# controller.net
KiCad netlist of a schematic drawn in EAGLE
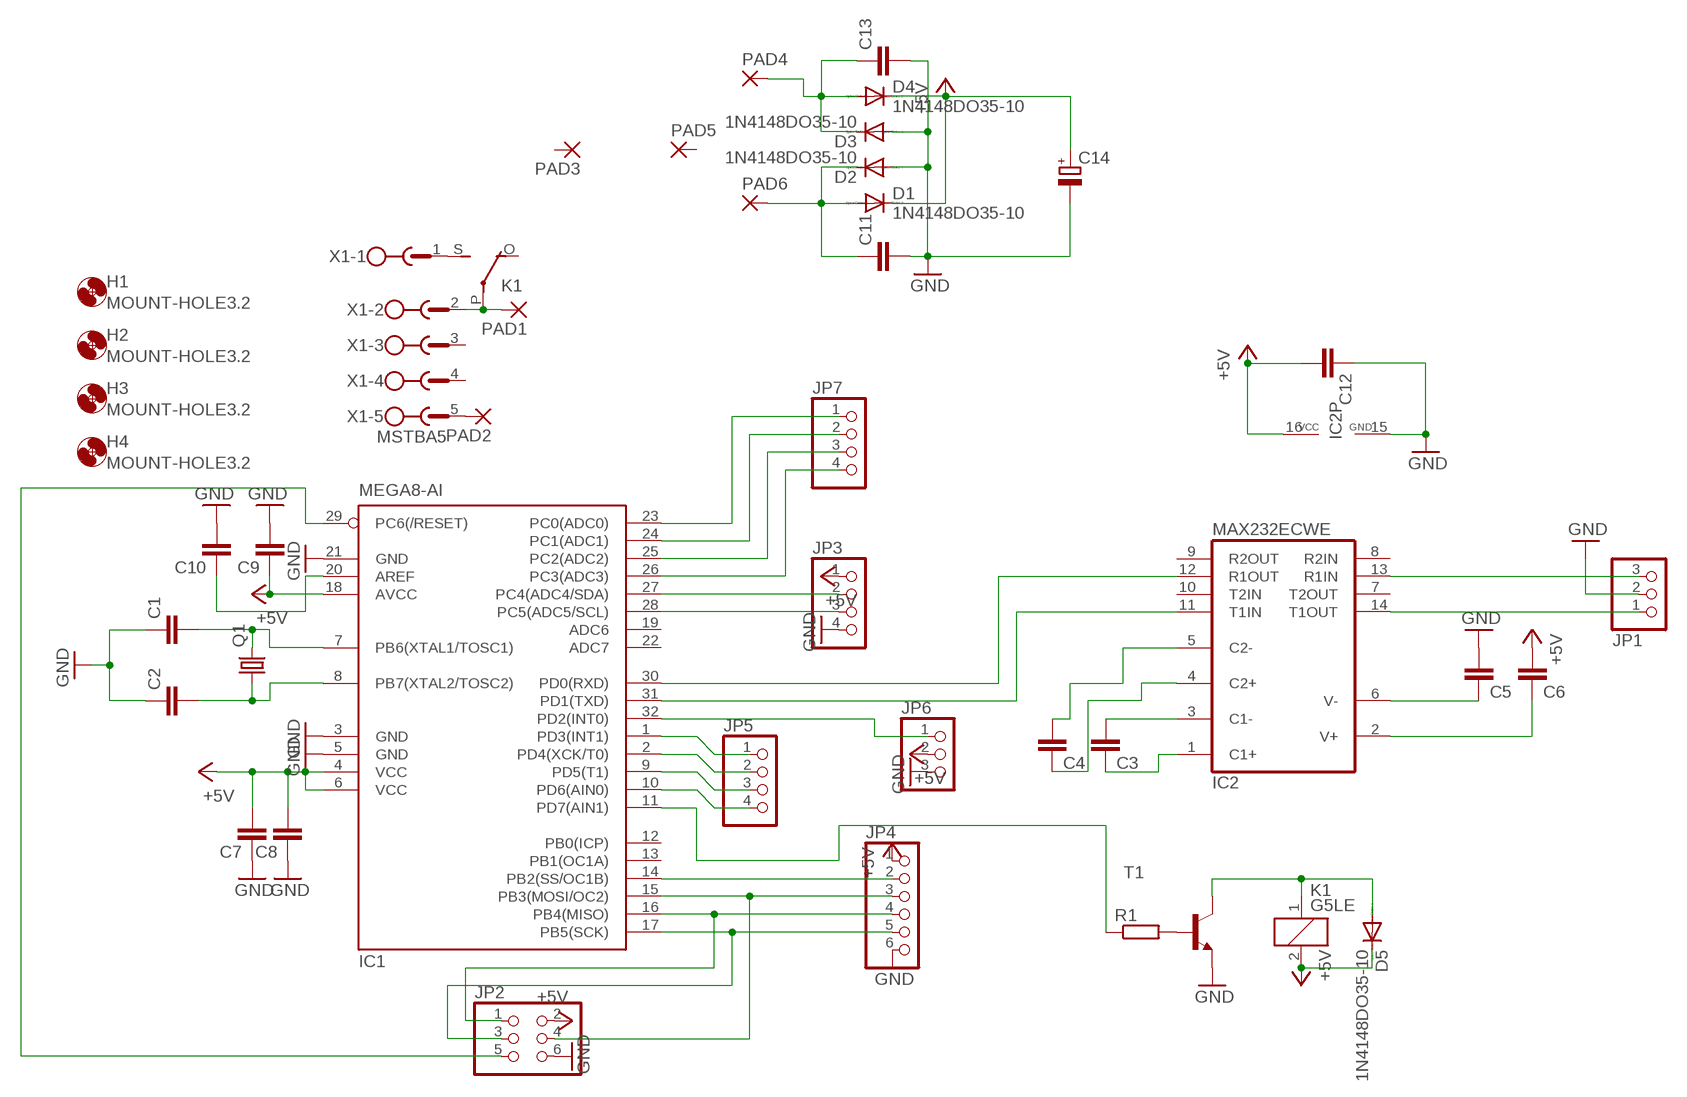
[diagram p0: schematic, sheet 1]

(export (version "E")
  (design (tool "Eeschema 10.0.6"))
  (components
    (comp (ref "C1")
      (value "C-EUC0805")
      (footprint "eagle-import:C0805")
      (libsource (lib "eagle-import") (part "C-EUC0805"))
    )
    (comp (ref "C2")
      (value "C-EUC0805")
      (footprint "eagle-import:C0805")
      (libsource (lib "eagle-import") (part "C-EUC0805"))
    )
    (comp (ref "C3")
      (value "C-EUC0805")
      (footprint "eagle-import:C0805")
      (libsource (lib "eagle-import") (part "C-EUC0805"))
    )
    (comp (ref "C4")
      (value "C-EUC0805")
      (footprint "eagle-import:C0805")
      (libsource (lib "eagle-import") (part "C-EUC0805"))
    )
    (comp (ref "C5")
      (value "C-EUC0805")
      (footprint "eagle-import:C0805")
      (libsource (lib "eagle-import") (part "C-EUC0805"))
    )
    (comp (ref "C6")
      (value "C-EUC0805")
      (footprint "eagle-import:C0805")
      (libsource (lib "eagle-import") (part "C-EUC0805"))
    )
    (comp (ref "C7")
      (value "C-EUC0805")
      (footprint "eagle-import:C0805")
      (libsource (lib "eagle-import") (part "C-EUC0805"))
    )
    (comp (ref "C8")
      (value "C-EUC0805")
      (footprint "eagle-import:C0805")
      (libsource (lib "eagle-import") (part "C-EUC0805"))
    )
    (comp (ref "C9")
      (value "C-EUC0805")
      (footprint "eagle-import:C0805")
      (libsource (lib "eagle-import") (part "C-EUC0805"))
    )
    (comp (ref "C10")
      (value "C-EUC0805")
      (footprint "eagle-import:C0805")
      (libsource (lib "eagle-import") (part "C-EUC0805"))
    )
    (comp (ref "C11")
      (value "C-EU050-025X075")
      (footprint "eagle-import:C050-025X075")
      (libsource (lib "eagle-import") (part "C-EU050-025X075"))
    )
    (comp (ref "C12")
      (value "C-EUC0805")
      (footprint "eagle-import:C0805")
      (libsource (lib "eagle-import") (part "C-EUC0805"))
    )
    (comp (ref "C13")
      (value "C-EU050-025X075")
      (footprint "eagle-import:C050-025X075")
      (libsource (lib "eagle-import") (part "C-EU050-025X075"))
    )
    (comp (ref "C14")
      (value "CPOL-EUE7.5-18")
      (footprint "eagle-import:E7,5-18")
      (libsource (lib "eagle-import") (part "CPOL-EUE7.5-18"))
    )
    (comp (ref "D1")
      (value "1N4148DO35-10")
      (footprint "eagle-import:DO35-10")
      (libsource (lib "eagle-import") (part "1N4148DO35-10"))
    )
    (comp (ref "D2")
      (value "1N4148DO35-10")
      (footprint "eagle-import:DO35-10")
      (libsource (lib "eagle-import") (part "1N4148DO35-10"))
    )
    (comp (ref "D3")
      (value "1N4148DO35-10")
      (footprint "eagle-import:DO35-10")
      (libsource (lib "eagle-import") (part "1N4148DO35-10"))
    )
    (comp (ref "D4")
      (value "1N4148DO35-10")
      (footprint "eagle-import:DO35-10")
      (libsource (lib "eagle-import") (part "1N4148DO35-10"))
    )
    (comp (ref "D5")
      (value "1N4148DO35-10")
      (footprint "eagle-import:DO35-10")
      (libsource (lib "eagle-import") (part "1N4148DO35-10"))
    )
    (comp (ref "H1")
      (value "MOUNT-HOLE3.2")
      (footprint "eagle-import:3,2")
      (libsource (lib "eagle-import") (part "MOUNT-HOLE3.2"))
    )
    (comp (ref "H2")
      (value "MOUNT-HOLE3.2")
      (footprint "eagle-import:3,2")
      (libsource (lib "eagle-import") (part "MOUNT-HOLE3.2"))
    )
    (comp (ref "H3")
      (value "MOUNT-HOLE3.2")
      (footprint "eagle-import:3,2")
      (libsource (lib "eagle-import") (part "MOUNT-HOLE3.2"))
    )
    (comp (ref "H4")
      (value "MOUNT-HOLE3.2")
      (footprint "eagle-import:3,2")
      (libsource (lib "eagle-import") (part "MOUNT-HOLE3.2"))
    )
    (comp (ref "IC1")
      (value "MEGA8-AI")
      (footprint "eagle-import:TQFP32-08")
      (fields (field (name "MPN") "ATMEGA8-16AU"))
      (libsource (lib "eagle-import") (part "MEGA8-AI"))
    )
    (comp (ref "IC2")
      (value "MAX232ECWE")
      (footprint "eagle-import:SO16")
      (libsource (lib "eagle-import") (part "MAX232ECWE"))
    )
    (comp (ref "JP1")
      (value "PINHD-1X3")
      (footprint "eagle-import:1X03")
      (libsource (lib "eagle-import") (part "PINHD-1X3"))
    )
    (comp (ref "JP2")
      (value "PINHD-2X3")
      (footprint "eagle-import:2X03")
      (libsource (lib "eagle-import") (part "PINHD-2X3"))
    )
    (comp (ref "JP3")
      (value "PINHD-1X4")
      (footprint "eagle-import:1X04")
      (libsource (lib "eagle-import") (part "PINHD-1X4"))
    )
    (comp (ref "JP4")
      (value "PINHD-1X6")
      (footprint "eagle-import:1X06")
      (libsource (lib "eagle-import") (part "PINHD-1X6"))
    )
    (comp (ref "JP5")
      (value "PINHD-1X4")
      (footprint "eagle-import:1X04")
      (libsource (lib "eagle-import") (part "PINHD-1X4"))
    )
    (comp (ref "JP6")
      (value "PINHD-1X3")
      (footprint "eagle-import:1X03")
      (libsource (lib "eagle-import") (part "PINHD-1X3"))
    )
    (comp (ref "JP7")
      (value "PINHD-1X4")
      (footprint "eagle-import:1X04")
      (libsource (lib "eagle-import") (part "PINHD-1X4"))
    )
    (comp (ref "K1")
      (value "G5LE")
      (footprint "eagle-import:G5LE")
      (libsource (lib "eagle-import") (part "G5LE"))
    )
    (comp (ref "PAD1")
      (value "3,81/1,4")
      (footprint "eagle-import:3,81_1,4")
      (libsource (lib "eagle-import") (part "3,81/1,4"))
    )
    (comp (ref "PAD2")
      (value "3,81/1,4")
      (footprint "eagle-import:3,81_1,4")
      (libsource (lib "eagle-import") (part "3,81/1,4"))
    )
    (comp (ref "PAD3")
      (value "3,81/1,4")
      (footprint "eagle-import:3,81_1,4")
      (libsource (lib "eagle-import") (part "3,81/1,4"))
    )
    (comp (ref "PAD4")
      (value "3,81/1,4")
      (footprint "eagle-import:3,81_1,4")
      (libsource (lib "eagle-import") (part "3,81/1,4"))
    )
    (comp (ref "PAD5")
      (value "3,81/1,4")
      (footprint "eagle-import:3,81_1,4")
      (libsource (lib "eagle-import") (part "3,81/1,4"))
    )
    (comp (ref "PAD6")
      (value "3,81/1,4")
      (footprint "eagle-import:3,81_1,4")
      (libsource (lib "eagle-import") (part "3,81/1,4"))
    )
    (comp (ref "Q1")
      (value "CRYSTALHC49S")
      (footprint "eagle-import:HC49_S")
      (fields (field (name "OC_FARNELL") "1667008"))
      (libsource (lib "eagle-import") (part "CRYSTALHC49S"))
    )
    (comp (ref "R1")
      (value "R-EU_0207/10")
      (footprint "eagle-import:0207_10")
      (libsource (lib "eagle-import") (part "R-EU_0207/10"))
    )
    (comp (ref "T1")
      (value "BC547A-NPN-TO92-CBE")
      (footprint "eagle-import:TO92-CBE")
      (libsource (lib "eagle-import") (part "-NPN-TO92-CBEBC547A"))
    )
    (comp (ref "X1")
      (value "MSTBA5")
      (footprint "eagle-import:MSTBA5")
      (fields (field (name "MPN") "1757271"))
      (libsource (lib "eagle-import") (part "MSTBA5"))
    )
  )
  (nets
    (net (code "1") (name "+5V") (class "Default")
      (node (ref "C12") (pin "2") (pinfunction "2_2") (pintype "passive"))
      (node (ref "C14") (pin "+") (pinfunction "+_+") (pintype "passive"))
      (node (ref "C6") (pin "2") (pinfunction "2_2") (pintype "passive"))
      (node (ref "C7") (pin "2") (pinfunction "2_2") (pintype "passive"))
      (node (ref "C8") (pin "2") (pinfunction "2_2") (pintype "passive"))
      (node (ref "C9") (pin "1") (pinfunction "1_1") (pintype "passive"))
      (node (ref "D1") (pin "C") (pinfunction "C_C") (pintype "passive"))
      (node (ref "D4") (pin "C") (pinfunction "C_C") (pintype "passive"))
      (node (ref "D5") (pin "C") (pinfunction "C_C") (pintype "passive"))
      (node (ref "IC1") (pin "18") (pinfunction "AVCC_18") (pintype "power_in"))
      (node (ref "IC1") (pin "4") (pinfunction "VCC_4") (pintype "power_in"))
      (node (ref "IC1") (pin "6") (pinfunction "VCC_6") (pintype "power_in"))
      (node (ref "IC2") (pin "16") (pinfunction "VCC_16") (pintype "power_in"))
      (node (ref "JP2") (pin "2") (pinfunction "2_2") (pintype "passive"))
      (node (ref "JP3") (pin "1") (pinfunction "1_1") (pintype "passive"))
      (node (ref "JP4") (pin "1") (pinfunction "1_1") (pintype "passive"))
      (node (ref "JP6") (pin "2") (pinfunction "2_2") (pintype "passive"))
      (node (ref "K1") (pin "2") (pinfunction "2_2") (pintype "passive"))
    )
    (net (code "2") (name "GND") (class "Default")
      (node (ref "C1") (pin "1") (pinfunction "1_1") (pintype "passive"))
      (node (ref "C10") (pin "2") (pinfunction "2_2") (pintype "passive"))
      (node (ref "C11") (pin "2") (pinfunction "2_2") (pintype "passive"))
      (node (ref "C12") (pin "1") (pinfunction "1_1") (pintype "passive"))
      (node (ref "C13") (pin "2") (pinfunction "2_2") (pintype "passive"))
      (node (ref "C14") (pin "-") (pinfunction "-_-") (pintype "passive"))
      (node (ref "C2") (pin "1") (pinfunction "1_1") (pintype "passive"))
      (node (ref "C5") (pin "2") (pinfunction "2_2") (pintype "passive"))
      (node (ref "C7") (pin "1") (pinfunction "1_1") (pintype "passive"))
      (node (ref "C8") (pin "1") (pinfunction "1_1") (pintype "passive"))
      (node (ref "C9") (pin "2") (pinfunction "2_2") (pintype "passive"))
      (node (ref "D2") (pin "A") (pinfunction "A_A") (pintype "passive"))
      (node (ref "D3") (pin "A") (pinfunction "A_A") (pintype "passive"))
      (node (ref "IC1") (pin "21") (pinfunction "GND_21") (pintype "power_in"))
      (node (ref "IC1") (pin "3") (pinfunction "GND_3") (pintype "power_in"))
      (node (ref "IC1") (pin "5") (pinfunction "GND_5") (pintype "power_in"))
      (node (ref "IC2") (pin "15") (pinfunction "GND_15") (pintype "power_in"))
      (node (ref "JP1") (pin "2") (pinfunction "2_2") (pintype "passive"))
      (node (ref "JP2") (pin "6") (pinfunction "6_6") (pintype "passive"))
      (node (ref "JP3") (pin "4") (pinfunction "4_4") (pintype "passive"))
      (node (ref "JP4") (pin "6") (pinfunction "6_6") (pintype "passive"))
      (node (ref "JP6") (pin "3") (pinfunction "3_3") (pintype "passive"))
      (node (ref "T1") (pin "E") (pinfunction "E_E") (pintype "passive"))
    )
    (net (code "3") (name "Net-(D5-PadA)") (class "Default")
      (node (ref "D5") (pin "A") (pinfunction "A_A") (pintype "passive"))
      (node (ref "K1") (pin "1") (pinfunction "1_1") (pintype "passive"))
      (node (ref "T1") (pin "C") (pinfunction "C_C") (pintype "passive"))
    )
    (net (code "4") (name "Net-(IC1-AREF)") (class "Default")
      (node (ref "C10") (pin "1") (pinfunction "1_1") (pintype "passive"))
      (node (ref "IC1") (pin "20") (pinfunction "AREF_20") (pintype "passive"))
    )
    (net (code "5") (name "Net-(IC1-PB2(SS{slash}OC1B))") (class "Default")
      (node (ref "IC1") (pin "14") (pinfunction "PB2(SS/OC1B)_14") (pintype "bidirectional"))
      (node (ref "JP4") (pin "2") (pinfunction "2_2") (pintype "passive"))
    )
    (net (code "6") (name "Net-(IC1-PB3(MOSI{slash}OC2))") (class "Default")
      (node (ref "IC1") (pin "15") (pinfunction "PB3(MOSI/OC2)_15") (pintype "bidirectional"))
      (node (ref "JP2") (pin "4") (pinfunction "4_4") (pintype "passive"))
      (node (ref "JP4") (pin "3") (pinfunction "3_3") (pintype "passive"))
    )
    (net (code "7") (name "Net-(IC1-PB4(MISO))") (class "Default")
      (node (ref "IC1") (pin "16") (pinfunction "PB4(MISO)_16") (pintype "bidirectional"))
      (node (ref "JP2") (pin "1") (pinfunction "1_1") (pintype "passive"))
      (node (ref "JP4") (pin "4") (pinfunction "4_4") (pintype "passive"))
    )
    (net (code "8") (name "Net-(IC1-PB5(SCK))") (class "Default")
      (node (ref "IC1") (pin "17") (pinfunction "PB5(SCK)_17") (pintype "bidirectional"))
      (node (ref "JP2") (pin "3") (pinfunction "3_3") (pintype "passive"))
      (node (ref "JP4") (pin "5") (pinfunction "5_5") (pintype "passive"))
    )
    (net (code "9") (name "Net-(IC1-PB6(XTAL1{slash}TOSC1))") (class "Default")
      (node (ref "C1") (pin "2") (pinfunction "2_2") (pintype "passive"))
      (node (ref "IC1") (pin "7") (pinfunction "PB6(XTAL1/TOSC1)_7") (pintype "bidirectional"))
      (node (ref "Q1") (pin "2") (pinfunction "2_2") (pintype "passive"))
    )
    (net (code "10") (name "Net-(IC1-PB7(XTAL2{slash}TOSC2))") (class "Default")
      (node (ref "C2") (pin "2") (pinfunction "2_2") (pintype "passive"))
      (node (ref "IC1") (pin "8") (pinfunction "PB7(XTAL2/TOSC2)_8") (pintype "bidirectional"))
      (node (ref "Q1") (pin "1") (pinfunction "1_1") (pintype "passive"))
    )
    (net (code "11") (name "Net-(IC1-PC0(ADC0))") (class "Default")
      (node (ref "IC1") (pin "23") (pinfunction "PC0(ADC0)_23") (pintype "bidirectional"))
      (node (ref "JP7") (pin "1") (pinfunction "1_1") (pintype "passive"))
    )
    (net (code "12") (name "Net-(IC1-PC1(ADC1))") (class "Default")
      (node (ref "IC1") (pin "24") (pinfunction "PC1(ADC1)_24") (pintype "bidirectional"))
      (node (ref "JP7") (pin "2") (pinfunction "2_2") (pintype "passive"))
    )
    (net (code "13") (name "Net-(IC1-PC2(ADC2))") (class "Default")
      (node (ref "IC1") (pin "25") (pinfunction "PC2(ADC2)_25") (pintype "bidirectional"))
      (node (ref "JP7") (pin "3") (pinfunction "3_3") (pintype "passive"))
    )
    (net (code "14") (name "Net-(IC1-PC3(ADC3))") (class "Default")
      (node (ref "IC1") (pin "26") (pinfunction "PC3(ADC3)_26") (pintype "bidirectional"))
      (node (ref "JP7") (pin "4") (pinfunction "4_4") (pintype "passive"))
    )
    (net (code "15") (name "Net-(IC1-PC4(ADC4{slash}SDA))") (class "Default")
      (node (ref "IC1") (pin "27") (pinfunction "PC4(ADC4/SDA)_27") (pintype "bidirectional"))
      (node (ref "JP3") (pin "2") (pinfunction "2_2") (pintype "passive"))
    )
    (net (code "16") (name "Net-(IC1-PC5(ADC5{slash}SCL))") (class "Default")
      (node (ref "IC1") (pin "28") (pinfunction "PC5(ADC5/SCL)_28") (pintype "bidirectional"))
      (node (ref "JP3") (pin "3") (pinfunction "3_3") (pintype "passive"))
    )
    (net (code "17") (name "Net-(IC1-PC6({slash}RESET))") (class "Default")
      (node (ref "IC1") (pin "29") (pinfunction "PC6(/RESET)_29") (pintype "bidirectional"))
      (node (ref "JP2") (pin "5") (pinfunction "5_5") (pintype "passive"))
    )
    (net (code "18") (name "Net-(IC1-PD0(RXD))") (class "Default")
      (node (ref "IC1") (pin "30") (pinfunction "PD0(RXD)_30") (pintype "bidirectional"))
      (node (ref "IC2") (pin "12") (pinfunction "R1OUT_12") (pintype "output"))
    )
    (net (code "19") (name "Net-(IC1-PD1(TXD))") (class "Default")
      (node (ref "IC1") (pin "31") (pinfunction "PD1(TXD)_31") (pintype "bidirectional"))
      (node (ref "IC2") (pin "11") (pinfunction "T1IN_11") (pintype "input"))
    )
    (net (code "20") (name "Net-(IC1-PD2(INT0))") (class "Default")
      (node (ref "IC1") (pin "32") (pinfunction "PD2(INT0)_32") (pintype "bidirectional"))
      (node (ref "JP6") (pin "1") (pinfunction "1_1") (pintype "passive"))
    )
    (net (code "21") (name "Net-(IC1-PD3(INT1))") (class "Default")
      (node (ref "IC1") (pin "1") (pinfunction "PD3(INT1)_1") (pintype "bidirectional"))
      (node (ref "JP5") (pin "1") (pinfunction "1_1") (pintype "passive"))
    )
    (net (code "22") (name "Net-(IC1-PD4(XCK{slash}T0))") (class "Default")
      (node (ref "IC1") (pin "2") (pinfunction "PD4(XCK/T0)_2") (pintype "bidirectional"))
      (node (ref "JP5") (pin "2") (pinfunction "2_2") (pintype "passive"))
    )
    (net (code "23") (name "Net-(IC1-PD5(T1))") (class "Default")
      (node (ref "IC1") (pin "9") (pinfunction "PD5(T1)_9") (pintype "bidirectional"))
      (node (ref "JP5") (pin "3") (pinfunction "3_3") (pintype "passive"))
    )
    (net (code "24") (name "Net-(IC1-PD6(AIN0))") (class "Default")
      (node (ref "IC1") (pin "10") (pinfunction "PD6(AIN0)_10") (pintype "bidirectional"))
      (node (ref "JP5") (pin "4") (pinfunction "4_4") (pintype "passive"))
    )
    (net (code "25") (name "Net-(IC1-PD7(AIN1))") (class "Default")
      (node (ref "IC1") (pin "11") (pinfunction "PD7(AIN1)_11") (pintype "bidirectional"))
      (node (ref "R1") (pin "1") (pinfunction "1_1") (pintype "passive"))
    )
    (net (code "26") (name "Net-(IC2A-C1+)") (class "Default")
      (node (ref "C3") (pin "1") (pinfunction "1_1") (pintype "passive"))
      (node (ref "IC2") (pin "1") (pinfunction "C1+_1") (pintype "bidirectional"))
    )
    (net (code "27") (name "Net-(IC2A-C1-)") (class "Default")
      (node (ref "C3") (pin "2") (pinfunction "2_2") (pintype "passive"))
      (node (ref "IC2") (pin "3") (pinfunction "C1-_3") (pintype "bidirectional"))
    )
    (net (code "28") (name "Net-(IC2A-C2+)") (class "Default")
      (node (ref "C4") (pin "1") (pinfunction "1_1") (pintype "passive"))
      (node (ref "IC2") (pin "4") (pinfunction "C2+_4") (pintype "bidirectional"))
    )
    (net (code "29") (name "Net-(IC2A-C2-)") (class "Default")
      (node (ref "C4") (pin "2") (pinfunction "2_2") (pintype "passive"))
      (node (ref "IC2") (pin "5") (pinfunction "C2-_5") (pintype "bidirectional"))
    )
    (net (code "30") (name "Net-(IC2A-R1IN)") (class "Default")
      (node (ref "IC2") (pin "13") (pinfunction "R1IN_13") (pintype "input"))
      (node (ref "JP1") (pin "3") (pinfunction "3_3") (pintype "passive"))
    )
    (net (code "31") (name "Net-(IC2A-T1OUT)") (class "Default")
      (node (ref "IC2") (pin "14") (pinfunction "T1OUT_14") (pintype "output"))
      (node (ref "JP1") (pin "1") (pinfunction "1_1") (pintype "passive"))
    )
    (net (code "32") (name "Net-(IC2A-V+)") (class "Default")
      (node (ref "C6") (pin "1") (pinfunction "1_1") (pintype "passive"))
      (node (ref "IC2") (pin "2") (pinfunction "V+_2") (pintype "bidirectional"))
    )
    (net (code "33") (name "Net-(IC2A-V-)") (class "Default")
      (node (ref "C5") (pin "1") (pinfunction "1_1") (pintype "passive"))
      (node (ref "IC2") (pin "6") (pinfunction "V-_6") (pintype "bidirectional"))
    )
    (net (code "34") (name "Net-(K1-PadS)") (class "Default")
      (node (ref "K1") (pin "S") (pinfunction "S_S") (pintype "passive"))
      (node (ref "X1") (pin "1") (pinfunction "1_1") (pintype "passive"))
    )
    (net (code "35") (name "Net-(PAD1-P)") (class "Default")
      (node (ref "K1") (pin "P") (pinfunction "P_P") (pintype "passive"))
      (node (ref "PAD1") (pin "1") (pinfunction "P_1") (pintype "passive"))
      (node (ref "X1") (pin "2") (pinfunction "1_2") (pintype "passive"))
    )
    (net (code "36") (name "Net-(PAD2-P)") (class "Default")
      (node (ref "PAD2") (pin "1") (pinfunction "P_1") (pintype "passive"))
      (node (ref "X1") (pin "5") (pinfunction "1_5") (pintype "passive"))
    )
    (net (code "37") (name "Net-(PAD4-P)") (class "Default")
      (node (ref "C13") (pin "1") (pinfunction "1_1") (pintype "passive"))
      (node (ref "D3") (pin "C") (pinfunction "C_C") (pintype "passive"))
      (node (ref "D4") (pin "A") (pinfunction "A_A") (pintype "passive"))
      (node (ref "PAD4") (pin "1") (pinfunction "P_1") (pintype "passive"))
    )
    (net (code "38") (name "Net-(PAD6-P)") (class "Default")
      (node (ref "C11") (pin "1") (pinfunction "1_1") (pintype "passive"))
      (node (ref "D1") (pin "A") (pinfunction "A_A") (pintype "passive"))
      (node (ref "D2") (pin "C") (pinfunction "C_C") (pintype "passive"))
      (node (ref "PAD6") (pin "1") (pinfunction "P_1") (pintype "passive"))
    )
    (net (code "39") (name "Net-(R1-Pad2)") (class "Default")
      (node (ref "R1") (pin "2") (pinfunction "2_2") (pintype "passive"))
      (node (ref "T1") (pin "B") (pinfunction "B_B") (pintype "passive"))
    )
    (net (code "40") (name "unconnected-(IC1-ADC6-Pad19)") (class "Default")
      (node (ref "IC1") (pin "19") (pinfunction "ADC6_19") (pintype "bidirectional"))
    )
    (net (code "41") (name "unconnected-(IC1-ADC7-Pad22)") (class "Default")
      (node (ref "IC1") (pin "22") (pinfunction "ADC7_22") (pintype "bidirectional"))
    )
    (net (code "42") (name "unconnected-(IC1-PB0(ICP)-Pad12)") (class "Default")
      (node (ref "IC1") (pin "12") (pinfunction "PB0(ICP)_12") (pintype "bidirectional"))
    )
    (net (code "43") (name "unconnected-(IC1-PB1(OC1A)-Pad13)") (class "Default")
      (node (ref "IC1") (pin "13") (pinfunction "PB1(OC1A)_13") (pintype "bidirectional"))
    )
    (net (code "44") (name "unconnected-(IC2A-R2IN-Pad8)") (class "Default")
      (node (ref "IC2") (pin "8") (pinfunction "R2IN_8") (pintype "input"))
    )
    (net (code "45") (name "unconnected-(IC2A-R2OUT-Pad9)") (class "Default")
      (node (ref "IC2") (pin "9") (pinfunction "R2OUT_9") (pintype "output"))
    )
    (net (code "46") (name "unconnected-(IC2A-T2IN-Pad10)") (class "Default")
      (node (ref "IC2") (pin "10") (pinfunction "T2IN_10") (pintype "input"))
    )
    (net (code "47") (name "unconnected-(IC2A-T2OUT-Pad7)") (class "Default")
      (node (ref "IC2") (pin "7") (pinfunction "T2OUT_7") (pintype "output"))
    )
    (net (code "48") (name "unconnected-(K1-PadO)") (class "Default")
      (node (ref "K1") (pin "O") (pinfunction "O_O") (pintype "passive"))
    )
    (net (code "49") (name "unconnected-(PAD3-P-Pad1)") (class "Default")
      (node (ref "PAD3") (pin "1") (pinfunction "P_1") (pintype "passive"))
    )
    (net (code "50") (name "unconnected-(PAD5-P-Pad1)") (class "Default")
      (node (ref "PAD5") (pin "1") (pinfunction "P_1") (pintype "passive"))
    )
    (net (code "51") (name "unconnected-(X1C-1-Pad3)") (class "Default")
      (node (ref "X1") (pin "3") (pinfunction "1_3") (pintype "passive"))
    )
    (net (code "52") (name "unconnected-(X1D-1-Pad4)") (class "Default")
      (node (ref "X1") (pin "4") (pinfunction "1_4") (pintype "passive"))
    )
  )
)
